# V2.net
KiCad netlist of a schematic drawn in EAGLE
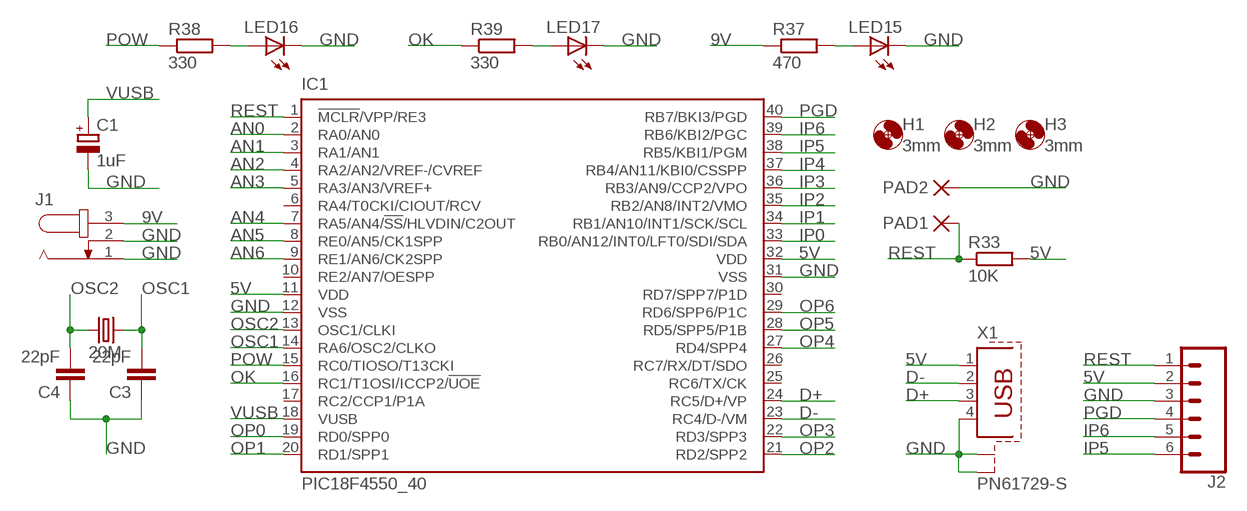
[diagram p0: schematic, sheet 1]
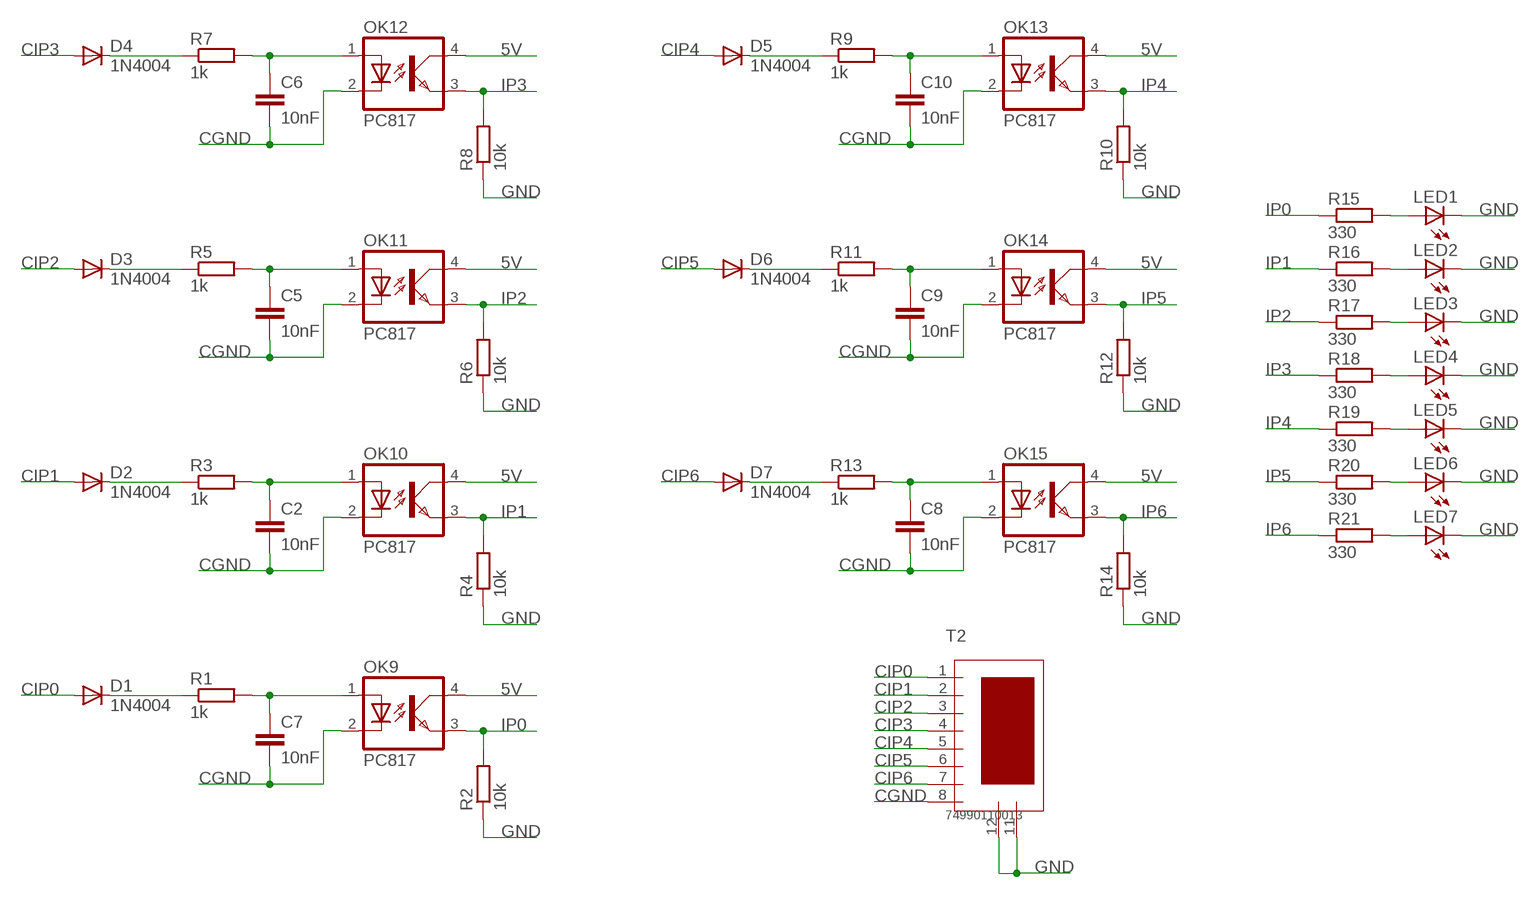
[diagram p1: schematic, sheet 2]
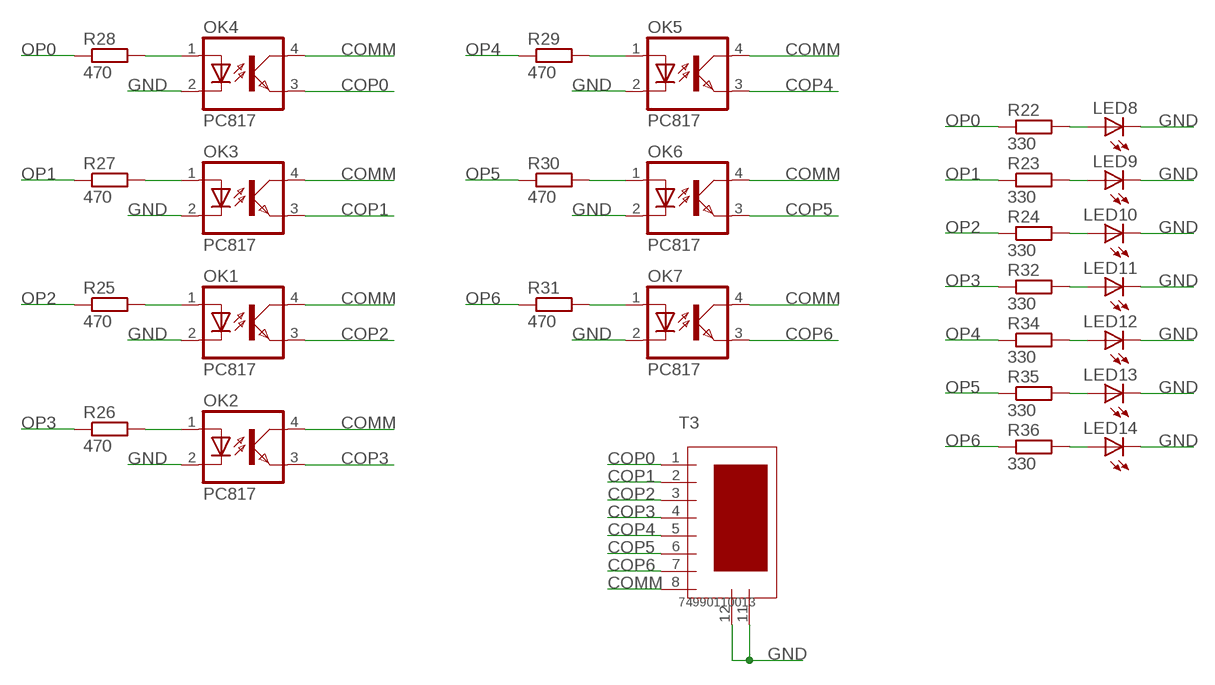
[diagram p2: schematic, sheet 3]
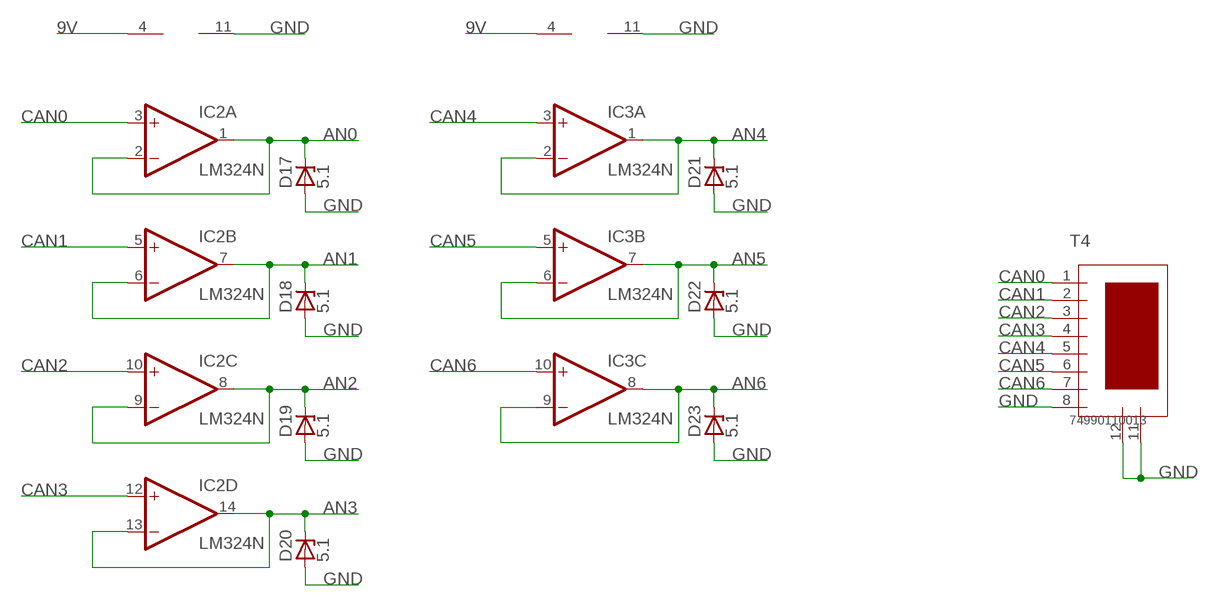
[diagram p3: schematic, sheet 4]

(export (version "E")
  (design (tool "Eeschema 10.0.6"))
  (components
    (comp (ref "LED8")
      (value "LED5MM")
      (footprint "eagle-import:LED5MM")
      (libsource (lib "eagle-import") (part "LED5MM"))
    )
    (comp (ref "LED9")
      (value "LED5MM")
      (footprint "eagle-import:LED5MM")
      (libsource (lib "eagle-import") (part "LED5MM"))
    )
    (comp (ref "LED10")
      (value "LED5MM")
      (footprint "eagle-import:LED5MM")
      (libsource (lib "eagle-import") (part "LED5MM"))
    )
    (comp (ref "LED11")
      (value "LED5MM")
      (footprint "eagle-import:LED5MM")
      (libsource (lib "eagle-import") (part "LED5MM"))
    )
    (comp (ref "LED12")
      (value "LED5MM")
      (footprint "eagle-import:LED5MM")
      (libsource (lib "eagle-import") (part "LED5MM"))
    )
    (comp (ref "LED13")
      (value "LED5MM")
      (footprint "eagle-import:LED5MM")
      (libsource (lib "eagle-import") (part "LED5MM"))
    )
    (comp (ref "LED14")
      (value "LED5MM")
      (footprint "eagle-import:LED5MM")
      (libsource (lib "eagle-import") (part "LED5MM"))
    )
    (comp (ref "OK1")
      (value "PC817")
      (footprint "eagle-import:DIL04")
      (fields (field (name "MPN") "PC817X4J000F"))
      (libsource (lib "eagle-import") (part "PC817"))
    )
    (comp (ref "OK2")
      (value "PC817")
      (footprint "eagle-import:DIL04")
      (fields (field (name "MPN") "PC817X4J000F"))
      (libsource (lib "eagle-import") (part "PC817"))
    )
    (comp (ref "OK3")
      (value "PC817")
      (footprint "eagle-import:DIL04")
      (fields (field (name "MPN") "PC817X4J000F"))
      (libsource (lib "eagle-import") (part "PC817"))
    )
    (comp (ref "OK4")
      (value "PC817")
      (footprint "eagle-import:DIL04")
      (fields (field (name "MPN") "PC817X4J000F"))
      (libsource (lib "eagle-import") (part "PC817"))
    )
    (comp (ref "OK5")
      (value "PC817")
      (footprint "eagle-import:DIL04")
      (fields (field (name "MPN") "PC817X4J000F"))
      (libsource (lib "eagle-import") (part "PC817"))
    )
    (comp (ref "OK6")
      (value "PC817")
      (footprint "eagle-import:DIL04")
      (fields (field (name "MPN") "PC817X4J000F"))
      (libsource (lib "eagle-import") (part "PC817"))
    )
    (comp (ref "OK7")
      (value "PC817")
      (footprint "eagle-import:DIL04")
      (fields (field (name "MPN") "PC817X4J000F"))
      (libsource (lib "eagle-import") (part "PC817"))
    )
    (comp (ref "R22")
      (value "330")
      (footprint "eagle-import:0207_10")
      (libsource (lib "eagle-import") (part "rcl_334_R-EU_0207/10"))
    )
    (comp (ref "R23")
      (value "330")
      (footprint "eagle-import:0207_10")
      (libsource (lib "eagle-import") (part "rcl_334_R-EU_0207/10"))
    )
    (comp (ref "R24")
      (value "330")
      (footprint "eagle-import:0207_10")
      (libsource (lib "eagle-import") (part "rcl_334_R-EU_0207/10"))
    )
    (comp (ref "R25")
      (value "470")
      (footprint "eagle-import:0207_10")
      (libsource (lib "eagle-import") (part "R-EU_0207/10"))
    )
    (comp (ref "R26")
      (value "470")
      (footprint "eagle-import:0207_10")
      (libsource (lib "eagle-import") (part "R-EU_0207/10"))
    )
    (comp (ref "R27")
      (value "470")
      (footprint "eagle-import:0207_10")
      (libsource (lib "eagle-import") (part "R-EU_0207/10"))
    )
    (comp (ref "R28")
      (value "470")
      (footprint "eagle-import:0207_10")
      (libsource (lib "eagle-import") (part "R-EU_0207/10"))
    )
    (comp (ref "R29")
      (value "470")
      (footprint "eagle-import:0207_10")
      (libsource (lib "eagle-import") (part "R-EU_0207/10"))
    )
    (comp (ref "R30")
      (value "470")
      (footprint "eagle-import:0207_10")
      (libsource (lib "eagle-import") (part "R-EU_0207/10"))
    )
    (comp (ref "R31")
      (value "470")
      (footprint "eagle-import:0207_10")
      (libsource (lib "eagle-import") (part "R-EU_0207/10"))
    )
    (comp (ref "R32")
      (value "330")
      (footprint "eagle-import:0207_10")
      (libsource (lib "eagle-import") (part "rcl_334_R-EU_0207/10"))
    )
    (comp (ref "R34")
      (value "330")
      (footprint "eagle-import:0207_10")
      (libsource (lib "eagle-import") (part "rcl_334_R-EU_0207/10"))
    )
    (comp (ref "R35")
      (value "330")
      (footprint "eagle-import:0207_10")
      (libsource (lib "eagle-import") (part "rcl_334_R-EU_0207/10"))
    )
    (comp (ref "R36")
      (value "330")
      (footprint "eagle-import:0207_10")
      (libsource (lib "eagle-import") (part "rcl_334_R-EU_0207/10"))
    )
    (comp (ref "T3")
      (value "74990110013")
      (footprint "eagle-import:01LAN_RJ45_10_00_STD")
      (libsource (lib "eagle-import") (part "74990110013"))
    )
    (comp (ref "C2")
      (value "10nF")
      (footprint "eagle-import:C5B2.5")
      (libsource (lib "eagle-import") (part "capacitor-wima_116_C5/2.5"))
    )
    (comp (ref "C5")
      (value "10nF")
      (footprint "eagle-import:C5B2.5")
      (libsource (lib "eagle-import") (part "capacitor-wima_116_C5/2.5"))
    )
    (comp (ref "C6")
      (value "10nF")
      (footprint "eagle-import:C5B2.5")
      (libsource (lib "eagle-import") (part "capacitor-wima_116_C5/2.5"))
    )
    (comp (ref "C7")
      (value "10nF")
      (footprint "eagle-import:C5B2.5")
      (libsource (lib "eagle-import") (part "capacitor-wima_116_C5/2.5"))
    )
    (comp (ref "C8")
      (value "10nF")
      (footprint "eagle-import:C5B2.5")
      (libsource (lib "eagle-import") (part "capacitor-wima_116_C5/2.5"))
    )
    (comp (ref "C9")
      (value "10nF")
      (footprint "eagle-import:C5B2.5")
      (libsource (lib "eagle-import") (part "capacitor-wima_116_C5/2.5"))
    )
    (comp (ref "C10")
      (value "10nF")
      (footprint "eagle-import:C5B2.5")
      (libsource (lib "eagle-import") (part "capacitor-wima_116_C5/2.5"))
    )
    (comp (ref "D1")
      (value "1N4004")
      (footprint "eagle-import:DO41-10")
      (libsource (lib "eagle-import") (part "1N4004"))
    )
    (comp (ref "D2")
      (value "1N4004")
      (footprint "eagle-import:DO41-10")
      (libsource (lib "eagle-import") (part "1N4004"))
    )
    (comp (ref "D3")
      (value "1N4004")
      (footprint "eagle-import:DO41-10")
      (libsource (lib "eagle-import") (part "1N4004"))
    )
    (comp (ref "D4")
      (value "1N4004")
      (footprint "eagle-import:DO41-10")
      (libsource (lib "eagle-import") (part "1N4004"))
    )
    (comp (ref "D5")
      (value "1N4004")
      (footprint "eagle-import:DO41-10")
      (libsource (lib "eagle-import") (part "1N4004"))
    )
    (comp (ref "D6")
      (value "1N4004")
      (footprint "eagle-import:DO41-10")
      (libsource (lib "eagle-import") (part "1N4004"))
    )
    (comp (ref "D7")
      (value "1N4004")
      (footprint "eagle-import:DO41-10")
      (libsource (lib "eagle-import") (part "1N4004"))
    )
    (comp (ref "LED1")
      (value "LED5MM")
      (footprint "eagle-import:LED5MM")
      (libsource (lib "eagle-import") (part "LED5MM"))
    )
    (comp (ref "LED2")
      (value "LED5MM")
      (footprint "eagle-import:LED5MM")
      (libsource (lib "eagle-import") (part "LED5MM"))
    )
    (comp (ref "LED3")
      (value "LED5MM")
      (footprint "eagle-import:LED5MM")
      (libsource (lib "eagle-import") (part "LED5MM"))
    )
    (comp (ref "LED4")
      (value "LED5MM")
      (footprint "eagle-import:LED5MM")
      (libsource (lib "eagle-import") (part "LED5MM"))
    )
    (comp (ref "LED5")
      (value "LED5MM")
      (footprint "eagle-import:LED5MM")
      (libsource (lib "eagle-import") (part "LED5MM"))
    )
    (comp (ref "LED6")
      (value "LED5MM")
      (footprint "eagle-import:LED5MM")
      (libsource (lib "eagle-import") (part "LED5MM"))
    )
    (comp (ref "LED7")
      (value "LED5MM")
      (footprint "eagle-import:LED5MM")
      (libsource (lib "eagle-import") (part "LED5MM"))
    )
    (comp (ref "OK9")
      (value "PC817")
      (footprint "eagle-import:DIL04")
      (fields (field (name "MPN") "PC817X4J000F"))
      (libsource (lib "eagle-import") (part "PC817"))
    )
    (comp (ref "OK10")
      (value "PC817")
      (footprint "eagle-import:DIL04")
      (fields (field (name "MPN") "PC817X4J000F"))
      (libsource (lib "eagle-import") (part "PC817"))
    )
    (comp (ref "OK11")
      (value "PC817")
      (footprint "eagle-import:DIL04")
      (fields (field (name "MPN") "PC817X4J000F"))
      (libsource (lib "eagle-import") (part "PC817"))
    )
    (comp (ref "OK12")
      (value "PC817")
      (footprint "eagle-import:DIL04")
      (fields (field (name "MPN") "PC817X4J000F"))
      (libsource (lib "eagle-import") (part "PC817"))
    )
    (comp (ref "OK13")
      (value "PC817")
      (footprint "eagle-import:DIL04")
      (fields (field (name "MPN") "PC817X4J000F"))
      (libsource (lib "eagle-import") (part "PC817"))
    )
    (comp (ref "OK14")
      (value "PC817")
      (footprint "eagle-import:DIL04")
      (fields (field (name "MPN") "PC817X4J000F"))
      (libsource (lib "eagle-import") (part "PC817"))
    )
    (comp (ref "OK15")
      (value "PC817")
      (footprint "eagle-import:DIL04")
      (fields (field (name "MPN") "PC817X4J000F"))
      (libsource (lib "eagle-import") (part "PC817"))
    )
    (comp (ref "R1")
      (value "1k")
      (footprint "eagle-import:0207_10")
      (libsource (lib "eagle-import") (part "rcl_334_R-EU_0207/10"))
    )
    (comp (ref "R2")
      (value "10k")
      (footprint "eagle-import:0207_10")
      (libsource (lib "eagle-import") (part "rcl_334_R-EU_0207/10"))
    )
    (comp (ref "R3")
      (value "1k")
      (footprint "eagle-import:0207_10")
      (libsource (lib "eagle-import") (part "rcl_334_R-EU_0207/10"))
    )
    (comp (ref "R4")
      (value "10k")
      (footprint "eagle-import:0207_10")
      (libsource (lib "eagle-import") (part "rcl_334_R-EU_0207/10"))
    )
    (comp (ref "R5")
      (value "1k")
      (footprint "eagle-import:0207_10")
      (libsource (lib "eagle-import") (part "rcl_334_R-EU_0207/10"))
    )
    (comp (ref "R6")
      (value "10k")
      (footprint "eagle-import:0207_10")
      (libsource (lib "eagle-import") (part "rcl_334_R-EU_0207/10"))
    )
    (comp (ref "R7")
      (value "1k")
      (footprint "eagle-import:0207_10")
      (libsource (lib "eagle-import") (part "rcl_334_R-EU_0207/10"))
    )
    (comp (ref "R8")
      (value "10k")
      (footprint "eagle-import:0207_10")
      (libsource (lib "eagle-import") (part "rcl_334_R-EU_0207/10"))
    )
    (comp (ref "R9")
      (value "1k")
      (footprint "eagle-import:0207_10")
      (libsource (lib "eagle-import") (part "rcl_334_R-EU_0207/10"))
    )
    (comp (ref "R10")
      (value "10k")
      (footprint "eagle-import:0207_10")
      (libsource (lib "eagle-import") (part "rcl_334_R-EU_0207/10"))
    )
    (comp (ref "R11")
      (value "1k")
      (footprint "eagle-import:0207_10")
      (libsource (lib "eagle-import") (part "rcl_334_R-EU_0207/10"))
    )
    (comp (ref "R12")
      (value "10k")
      (footprint "eagle-import:0207_10")
      (libsource (lib "eagle-import") (part "rcl_334_R-EU_0207/10"))
    )
    (comp (ref "R13")
      (value "1k")
      (footprint "eagle-import:0207_10")
      (libsource (lib "eagle-import") (part "rcl_334_R-EU_0207/10"))
    )
    (comp (ref "R14")
      (value "10k")
      (footprint "eagle-import:0207_10")
      (libsource (lib "eagle-import") (part "rcl_334_R-EU_0207/10"))
    )
    (comp (ref "R15")
      (value "330")
      (footprint "eagle-import:0207_10")
      (libsource (lib "eagle-import") (part "rcl_334_R-EU_0207/10"))
    )
    (comp (ref "R16")
      (value "330")
      (footprint "eagle-import:0207_10")
      (libsource (lib "eagle-import") (part "rcl_334_R-EU_0207/10"))
    )
    (comp (ref "R17")
      (value "330")
      (footprint "eagle-import:0207_10")
      (libsource (lib "eagle-import") (part "rcl_334_R-EU_0207/10"))
    )
    (comp (ref "R18")
      (value "330")
      (footprint "eagle-import:0207_10")
      (libsource (lib "eagle-import") (part "rcl_334_R-EU_0207/10"))
    )
    (comp (ref "R19")
      (value "330")
      (footprint "eagle-import:0207_10")
      (libsource (lib "eagle-import") (part "rcl_334_R-EU_0207/10"))
    )
    (comp (ref "R20")
      (value "330")
      (footprint "eagle-import:0207_10")
      (libsource (lib "eagle-import") (part "rcl_334_R-EU_0207/10"))
    )
    (comp (ref "R21")
      (value "330")
      (footprint "eagle-import:0207_10")
      (libsource (lib "eagle-import") (part "rcl_334_R-EU_0207/10"))
    )
    (comp (ref "T2")
      (value "74990110013")
      (footprint "eagle-import:01LAN_RJ45_10_00_STD")
      (libsource (lib "eagle-import") (part "74990110013"))
    )
    (comp (ref "D17")
      (value "5.1")
      (footprint "eagle-import:ZDIO-10")
      (libsource (lib "eagle-import") (part "ZENER-DIODEZD-10"))
    )
    (comp (ref "D18")
      (value "5.1")
      (footprint "eagle-import:ZDIO-10")
      (libsource (lib "eagle-import") (part "ZENER-DIODEZD-10"))
    )
    (comp (ref "D19")
      (value "5.1")
      (footprint "eagle-import:ZDIO-10")
      (libsource (lib "eagle-import") (part "ZENER-DIODEZD-10"))
    )
    (comp (ref "D20")
      (value "5.1")
      (footprint "eagle-import:ZDIO-10")
      (libsource (lib "eagle-import") (part "ZENER-DIODEZD-10"))
    )
    (comp (ref "D21")
      (value "5.1")
      (footprint "eagle-import:ZDIO-10")
      (libsource (lib "eagle-import") (part "ZENER-DIODEZD-10"))
    )
    (comp (ref "D22")
      (value "5.1")
      (footprint "eagle-import:ZDIO-10")
      (libsource (lib "eagle-import") (part "ZENER-DIODEZD-10"))
    )
    (comp (ref "D23")
      (value "5.1")
      (footprint "eagle-import:ZDIO-10")
      (libsource (lib "eagle-import") (part "ZENER-DIODEZD-10"))
    )
    (comp (ref "IC2")
      (value "LM324N")
      (footprint "eagle-import:DIL14")
      (libsource (lib "eagle-import") (part "LM324N"))
    )
    (comp (ref "IC3")
      (value "LM324N")
      (footprint "eagle-import:DIL14")
      (libsource (lib "eagle-import") (part "LM324N"))
    )
    (comp (ref "T4")
      (value "74990110013")
      (footprint "eagle-import:01LAN_RJ45_10_00_STD")
      (libsource (lib "eagle-import") (part "74990110013"))
    )
    (comp (ref "20M")
      (value "CRYSTALHC18U-V")
      (footprint "eagle-import:HC18U-V")
      (libsource (lib "eagle-import") (part "CRYSTALHC18U-V"))
    )
    (comp (ref "C1")
      (value "1uF")
      (footprint "eagle-import:E2-5")
      (libsource (lib "eagle-import") (part "CPOL-EUE2-5"))
    )
    (comp (ref "C3")
      (value "22pF")
      (footprint "eagle-import:C5B2.5")
      (libsource (lib "eagle-import") (part "C5/2.5"))
    )
    (comp (ref "C4")
      (value "22pF")
      (footprint "eagle-import:C5B2.5")
      (libsource (lib "eagle-import") (part "C5/2.5"))
    )
    (comp (ref "H1")
      (value "3mm")
      (footprint "eagle-import:3,0")
      (libsource (lib "eagle-import") (part "MOUNT-HOLE3.0"))
    )
    (comp (ref "H2")
      (value "3mm")
      (footprint "eagle-import:3,0")
      (libsource (lib "eagle-import") (part "MOUNT-HOLE3.0"))
    )
    (comp (ref "H3")
      (value "3mm")
      (footprint "eagle-import:3,0")
      (libsource (lib "eagle-import") (part "MOUNT-HOLE3.0"))
    )
    (comp (ref "IC1")
      (value "PIC18F4550_40")
      (footprint "eagle-import:DIL40")
      (fields (field (name "MF") "MICROCHIP") (field (name "MPN") "PIC18F4550-I/P"))
      (libsource (lib "eagle-import") (part "PIC18F4_40550"))
    )
    (comp (ref "J1")
      (value "JACK-PLUG0")
      (footprint "eagle-import:SPC4077")
      (libsource (lib "eagle-import") (part "JACK-PLUG0"))
    )
    (comp (ref "J2")
      (value "CONN_06LONGPADS")
      (footprint "eagle-import:1X06_LONGPADS")
      (libsource (lib "eagle-import") (part "CONN_06LONGPADS"))
    )
    (comp (ref "LED15")
      (value "LED5MM")
      (footprint "eagle-import:LED5MM")
      (libsource (lib "eagle-import") (part "LED5MM"))
    )
    (comp (ref "LED16")
      (value "LED5MM")
      (footprint "eagle-import:LED5MM")
      (libsource (lib "eagle-import") (part "LED5MM"))
    )
    (comp (ref "LED17")
      (value "LED5MM")
      (footprint "eagle-import:LED5MM")
      (libsource (lib "eagle-import") (part "LED5MM"))
    )
    (comp (ref "PAD1")
      (value "PAD-0320")
      (footprint "eagle-import:0320")
      (libsource (lib "eagle-import") (part "PAD-0320"))
    )
    (comp (ref "PAD2")
      (value "PAD-0320")
      (footprint "eagle-import:0320")
      (libsource (lib "eagle-import") (part "PAD-0320"))
    )
    (comp (ref "R33")
      (value "10K")
      (footprint "eagle-import:0207_10")
      (libsource (lib "eagle-import") (part "R-EU_0207/10"))
    )
    (comp (ref "R37")
      (value "470")
      (footprint "eagle-import:0207_10")
      (libsource (lib "eagle-import") (part "rcl_334_R-EU_0207/10"))
    )
    (comp (ref "R38")
      (value "330")
      (footprint "eagle-import:0207_10")
      (libsource (lib "eagle-import") (part "rcl_334_R-EU_0207/10"))
    )
    (comp (ref "R39")
      (value "330")
      (footprint "eagle-import:0207_10")
      (libsource (lib "eagle-import") (part "rcl_334_R-EU_0207/10"))
    )
    (comp (ref "X1")
      (value "PN61729-S")
      (footprint "eagle-import:PN61729-S")
      (libsource (lib "eagle-import") (part "PN61729-S"))
    )
  )
  (nets
    (net (code "1") (name "5V") (class "Default")
      (node (ref "IC1") (pin "11") (pinfunction "VDD_11") (pintype "power_in"))
      (node (ref "IC1") (pin "32") (pinfunction "VDD_32") (pintype "power_in"))
      (node (ref "J2") (pin "2") (pinfunction "2_2") (pintype "passive"))
      (node (ref "OK10") (pin "4") (pinfunction "COL_4") (pintype "passive"))
      (node (ref "OK11") (pin "4") (pinfunction "COL_4") (pintype "passive"))
      (node (ref "OK12") (pin "4") (pinfunction "COL_4") (pintype "passive"))
      (node (ref "OK13") (pin "4") (pinfunction "COL_4") (pintype "passive"))
      (node (ref "OK14") (pin "4") (pinfunction "COL_4") (pintype "passive"))
      (node (ref "OK15") (pin "4") (pinfunction "COL_4") (pintype "passive"))
      (node (ref "OK9") (pin "4") (pinfunction "COL_4") (pintype "passive"))
      (node (ref "R33") (pin "2") (pinfunction "2_2") (pintype "passive"))
      (node (ref "X1") (pin "1") (pinfunction "1_1") (pintype "passive"))
    )
    (net (code "2") (name "9V") (class "Default")
      (node (ref "IC2") (pin "4") (pinfunction "V+_4") (pintype "power_in"))
      (node (ref "IC3") (pin "4") (pinfunction "V+_4") (pintype "power_in"))
      (node (ref "J1") (pin "3") (pinfunction "3_3") (pintype "passive"))
      (node (ref "R37") (pin "1") (pinfunction "1_1") (pintype "passive"))
    )
    (net (code "3") (name "AN0") (class "Default")
      (node (ref "D17") (pin "C") (pinfunction "C_C") (pintype "passive"))
      (node (ref "IC1") (pin "2") (pinfunction "RA0/AN0_2") (pintype "bidirectional"))
      (node (ref "IC2") (pin "1") (pinfunction "OUT_1") (pintype "output"))
      (node (ref "IC2") (pin "2") (pinfunction "-IN_2") (pintype "input"))
    )
    (net (code "4") (name "AN1") (class "Default")
      (node (ref "D18") (pin "C") (pinfunction "C_C") (pintype "passive"))
      (node (ref "IC1") (pin "3") (pinfunction "RA1/AN1_3") (pintype "bidirectional"))
      (node (ref "IC2") (pin "6") (pinfunction "-IN_6") (pintype "input"))
      (node (ref "IC2") (pin "7") (pinfunction "OUT_7") (pintype "output"))
    )
    (net (code "5") (name "AN2") (class "Default")
      (node (ref "D19") (pin "C") (pinfunction "C_C") (pintype "passive"))
      (node (ref "IC1") (pin "4") (pinfunction "RA2/AN2/VREF-/CVREF_4") (pintype "bidirectional"))
      (node (ref "IC2") (pin "8") (pinfunction "OUT_8") (pintype "output"))
      (node (ref "IC2") (pin "9") (pinfunction "-IN_9") (pintype "input"))
    )
    (net (code "6") (name "AN3") (class "Default")
      (node (ref "D20") (pin "C") (pinfunction "C_C") (pintype "passive"))
      (node (ref "IC1") (pin "5") (pinfunction "RA3/AN3/VREF+_5") (pintype "bidirectional"))
      (node (ref "IC2") (pin "13") (pinfunction "-IN_13") (pintype "input"))
      (node (ref "IC2") (pin "14") (pinfunction "OUT_14") (pintype "output"))
    )
    (net (code "7") (name "AN4") (class "Default")
      (node (ref "D21") (pin "C") (pinfunction "C_C") (pintype "passive"))
      (node (ref "IC1") (pin "7") (pinfunction "RA5/AN4/~{SS}/HLVDIN/C2OUT_7") (pintype "bidirectional"))
      (node (ref "IC3") (pin "1") (pinfunction "OUT_1") (pintype "output"))
      (node (ref "IC3") (pin "2") (pinfunction "-IN_2") (pintype "input"))
    )
    (net (code "8") (name "AN5") (class "Default")
      (node (ref "D22") (pin "C") (pinfunction "C_C") (pintype "passive"))
      (node (ref "IC1") (pin "8") (pinfunction "RE0/AN5/CK1SPP_8") (pintype "bidirectional"))
      (node (ref "IC3") (pin "6") (pinfunction "-IN_6") (pintype "input"))
      (node (ref "IC3") (pin "7") (pinfunction "OUT_7") (pintype "output"))
    )
    (net (code "9") (name "AN6") (class "Default")
      (node (ref "D23") (pin "C") (pinfunction "C_C") (pintype "passive"))
      (node (ref "IC1") (pin "9") (pinfunction "RE1/AN6/CK2SPP_9") (pintype "bidirectional"))
      (node (ref "IC3") (pin "8") (pinfunction "OUT_8") (pintype "output"))
      (node (ref "IC3") (pin "9") (pinfunction "-IN_9") (pintype "input"))
    )
    (net (code "10") (name "CAN0") (class "Default")
      (node (ref "IC2") (pin "3") (pinfunction "+IN_3") (pintype "input"))
      (node (ref "T4") (pin "1") (pinfunction "1_1") (pintype "passive"))
    )
    (net (code "11") (name "CAN1") (class "Default")
      (node (ref "IC2") (pin "5") (pinfunction "+IN_5") (pintype "input"))
      (node (ref "T4") (pin "2") (pinfunction "2_2") (pintype "passive"))
    )
    (net (code "12") (name "CAN2") (class "Default")
      (node (ref "IC2") (pin "10") (pinfunction "+IN_10") (pintype "input"))
      (node (ref "T4") (pin "3") (pinfunction "3_3") (pintype "passive"))
    )
    (net (code "13") (name "CAN3") (class "Default")
      (node (ref "IC2") (pin "12") (pinfunction "+IN_12") (pintype "input"))
      (node (ref "T4") (pin "4") (pinfunction "4_4") (pintype "passive"))
    )
    (net (code "14") (name "CAN4") (class "Default")
      (node (ref "IC3") (pin "3") (pinfunction "+IN_3") (pintype "input"))
      (node (ref "T4") (pin "5") (pinfunction "5_5") (pintype "passive"))
    )
    (net (code "15") (name "CAN5") (class "Default")
      (node (ref "IC3") (pin "5") (pinfunction "+IN_5") (pintype "input"))
      (node (ref "T4") (pin "6") (pinfunction "6_6") (pintype "passive"))
    )
    (net (code "16") (name "CAN6") (class "Default")
      (node (ref "IC3") (pin "10") (pinfunction "+IN_10") (pintype "input"))
      (node (ref "T4") (pin "7") (pinfunction "8_7") (pintype "passive"))
    )
    (net (code "17") (name "CGND") (class "Default")
      (node (ref "C10") (pin "2") (pinfunction "2_2") (pintype "passive"))
      (node (ref "C2") (pin "2") (pinfunction "2_2") (pintype "passive"))
      (node (ref "C5") (pin "2") (pinfunction "2_2") (pintype "passive"))
      (node (ref "C6") (pin "2") (pinfunction "2_2") (pintype "passive"))
      (node (ref "C7") (pin "2") (pinfunction "2_2") (pintype "passive"))
      (node (ref "C8") (pin "2") (pinfunction "2_2") (pintype "passive"))
      (node (ref "C9") (pin "2") (pinfunction "2_2") (pintype "passive"))
      (node (ref "OK10") (pin "2") (pinfunction "C_2") (pintype "passive"))
      (node (ref "OK11") (pin "2") (pinfunction "C_2") (pintype "passive"))
      (node (ref "OK12") (pin "2") (pinfunction "C_2") (pintype "passive"))
      (node (ref "OK13") (pin "2") (pinfunction "C_2") (pintype "passive"))
      (node (ref "OK14") (pin "2") (pinfunction "C_2") (pintype "passive"))
      (node (ref "OK15") (pin "2") (pinfunction "C_2") (pintype "passive"))
      (node (ref "OK9") (pin "2") (pinfunction "C_2") (pintype "passive"))
      (node (ref "T2") (pin "8") (pinfunction "7_8") (pintype "passive"))
    )
    (net (code "18") (name "CIP0") (class "Default")
      (node (ref "D1") (pin "A") (pinfunction "A_A") (pintype "passive"))
      (node (ref "T2") (pin "1") (pinfunction "1_1") (pintype "passive"))
    )
    (net (code "19") (name "CIP1") (class "Default")
      (node (ref "D2") (pin "A") (pinfunction "A_A") (pintype "passive"))
      (node (ref "T2") (pin "2") (pinfunction "2_2") (pintype "passive"))
    )
    (net (code "20") (name "CIP2") (class "Default")
      (node (ref "D3") (pin "A") (pinfunction "A_A") (pintype "passive"))
      (node (ref "T2") (pin "3") (pinfunction "3_3") (pintype "passive"))
    )
    (net (code "21") (name "CIP3") (class "Default")
      (node (ref "D4") (pin "A") (pinfunction "A_A") (pintype "passive"))
      (node (ref "T2") (pin "4") (pinfunction "4_4") (pintype "passive"))
    )
    (net (code "22") (name "CIP4") (class "Default")
      (node (ref "D5") (pin "A") (pinfunction "A_A") (pintype "passive"))
      (node (ref "T2") (pin "5") (pinfunction "5_5") (pintype "passive"))
    )
    (net (code "23") (name "CIP5") (class "Default")
      (node (ref "D6") (pin "A") (pinfunction "A_A") (pintype "passive"))
      (node (ref "T2") (pin "6") (pinfunction "6_6") (pintype "passive"))
    )
    (net (code "24") (name "CIP6") (class "Default")
      (node (ref "D7") (pin "A") (pinfunction "A_A") (pintype "passive"))
      (node (ref "T2") (pin "7") (pinfunction "8_7") (pintype "passive"))
    )
    (net (code "25") (name "COMM") (class "Default")
      (node (ref "OK1") (pin "4") (pinfunction "COL_4") (pintype "passive"))
      (node (ref "OK2") (pin "4") (pinfunction "COL_4") (pintype "passive"))
      (node (ref "OK3") (pin "4") (pinfunction "COL_4") (pintype "passive"))
      (node (ref "OK4") (pin "4") (pinfunction "COL_4") (pintype "passive"))
      (node (ref "OK5") (pin "4") (pinfunction "COL_4") (pintype "passive"))
      (node (ref "OK6") (pin "4") (pinfunction "COL_4") (pintype "passive"))
      (node (ref "OK7") (pin "4") (pinfunction "COL_4") (pintype "passive"))
      (node (ref "T3") (pin "8") (pinfunction "7_8") (pintype "passive"))
    )
    (net (code "26") (name "COP0") (class "Default")
      (node (ref "OK4") (pin "3") (pinfunction "EMIT_3") (pintype "passive"))
      (node (ref "T3") (pin "1") (pinfunction "1_1") (pintype "passive"))
    )
    (net (code "27") (name "COP1") (class "Default")
      (node (ref "OK3") (pin "3") (pinfunction "EMIT_3") (pintype "passive"))
      (node (ref "T3") (pin "2") (pinfunction "2_2") (pintype "passive"))
    )
    (net (code "28") (name "COP2") (class "Default")
      (node (ref "OK1") (pin "3") (pinfunction "EMIT_3") (pintype "passive"))
      (node (ref "T3") (pin "3") (pinfunction "3_3") (pintype "passive"))
    )
    (net (code "29") (name "COP3") (class "Default")
      (node (ref "OK2") (pin "3") (pinfunction "EMIT_3") (pintype "passive"))
      (node (ref "T3") (pin "4") (pinfunction "4_4") (pintype "passive"))
    )
    (net (code "30") (name "COP4") (class "Default")
      (node (ref "OK5") (pin "3") (pinfunction "EMIT_3") (pintype "passive"))
      (node (ref "T3") (pin "5") (pinfunction "5_5") (pintype "passive"))
    )
    (net (code "31") (name "COP5") (class "Default")
      (node (ref "OK6") (pin "3") (pinfunction "EMIT_3") (pintype "passive"))
      (node (ref "T3") (pin "6") (pinfunction "6_6") (pintype "passive"))
    )
    (net (code "32") (name "COP6") (class "Default")
      (node (ref "OK7") (pin "3") (pinfunction "EMIT_3") (pintype "passive"))
      (node (ref "T3") (pin "7") (pinfunction "8_7") (pintype "passive"))
    )
    (net (code "33") (name "D+") (class "Default")
      (node (ref "IC1") (pin "24") (pinfunction "RC5/D+/VP_24") (pintype "bidirectional"))
      (node (ref "X1") (pin "3") (pinfunction "3_3") (pintype "passive"))
    )
    (net (code "34") (name "D-") (class "Default")
      (node (ref "IC1") (pin "23") (pinfunction "RC4/D-/VM_23") (pintype "bidirectional"))
      (node (ref "X1") (pin "2") (pinfunction "2_2") (pintype "passive"))
    )
    (net (code "35") (name "GND") (class "Default")
      (node (ref "C1") (pin "-") (pinfunction "-_-") (pintype "passive"))
      (node (ref "C3") (pin "1") (pinfunction "1_1") (pintype "passive"))
      (node (ref "C4") (pin "1") (pinfunction "1_1") (pintype "passive"))
      (node (ref "D17") (pin "A") (pinfunction "A_A") (pintype "passive"))
      (node (ref "D18") (pin "A") (pinfunction "A_A") (pintype "passive"))
      (node (ref "D19") (pin "A") (pinfunction "A_A") (pintype "passive"))
      (node (ref "D20") (pin "A") (pinfunction "A_A") (pintype "passive"))
      (node (ref "D21") (pin "A") (pinfunction "A_A") (pintype "passive"))
      (node (ref "D22") (pin "A") (pinfunction "A_A") (pintype "passive"))
      (node (ref "D23") (pin "A") (pinfunction "A_A") (pintype "passive"))
      (node (ref "IC1") (pin "12") (pinfunction "VSS_12") (pintype "power_in"))
      (node (ref "IC1") (pin "31") (pinfunction "VSS_31") (pintype "power_in"))
      (node (ref "IC2") (pin "11") (pinfunction "V-_11") (pintype "power_in"))
      (node (ref "IC3") (pin "11") (pinfunction "V-_11") (pintype "power_in"))
      (node (ref "J1") (pin "1") (pinfunction "1_1") (pintype "passive"))
      (node (ref "J1") (pin "2") (pinfunction "2_2") (pintype "passive"))
      (node (ref "J2") (pin "3") (pinfunction "3_3") (pintype "passive"))
      (node (ref "LED1") (pin "K") (pinfunction "C_K") (pintype "passive"))
      (node (ref "LED10") (pin "K") (pinfunction "C_K") (pintype "passive"))
      (node (ref "LED11") (pin "K") (pinfunction "C_K") (pintype "passive"))
      (node (ref "LED12") (pin "K") (pinfunction "C_K") (pintype "passive"))
      (node (ref "LED13") (pin "K") (pinfunction "C_K") (pintype "passive"))
      (node (ref "LED14") (pin "K") (pinfunction "C_K") (pintype "passive"))
      (node (ref "LED15") (pin "K") (pinfunction "C_K") (pintype "passive"))
      (node (ref "LED16") (pin "K") (pinfunction "C_K") (pintype "passive"))
      (node (ref "LED17") (pin "K") (pinfunction "C_K") (pintype "passive"))
      (node (ref "LED2") (pin "K") (pinfunction "C_K") (pintype "passive"))
      (node (ref "LED3") (pin "K") (pinfunction "C_K") (pintype "passive"))
      (node (ref "LED4") (pin "K") (pinfunction "C_K") (pintype "passive"))
      (node (ref "LED5") (pin "K") (pinfunction "C_K") (pintype "passive"))
      (node (ref "LED6") (pin "K") (pinfunction "C_K") (pintype "passive"))
      (node (ref "LED7") (pin "K") (pinfunction "C_K") (pintype "passive"))
      (node (ref "LED8") (pin "K") (pinfunction "C_K") (pintype "passive"))
      (node (ref "LED9") (pin "K") (pinfunction "C_K") (pintype "passive"))
      (node (ref "OK1") (pin "2") (pinfunction "C_2") (pintype "passive"))
      (node (ref "OK2") (pin "2") (pinfunction "C_2") (pintype "passive"))
      (node (ref "OK3") (pin "2") (pinfunction "C_2") (pintype "passive"))
      (node (ref "OK4") (pin "2") (pinfunction "C_2") (pintype "passive"))
      (node (ref "OK5") (pin "2") (pinfunction "C_2") (pintype "passive"))
      (node (ref "OK6") (pin "2") (pinfunction "C_2") (pintype "passive"))
      (node (ref "OK7") (pin "2") (pinfunction "C_2") (pintype "passive"))
      (node (ref "PAD2") (pin "P$1") (pinfunction "P_P$1") (pintype "passive"))
      (node (ref "R10") (pin "1") (pinfunction "1_1") (pintype "passive"))
      (node (ref "R12") (pin "1") (pinfunction "1_1") (pintype "passive"))
      (node (ref "R14") (pin "1") (pinfunction "1_1") (pintype "passive"))
      (node (ref "R2") (pin "1") (pinfunction "1_1") (pintype "passive"))
      (node (ref "R4") (pin "1") (pinfunction "1_1") (pintype "passive"))
      (node (ref "R6") (pin "1") (pinfunction "1_1") (pintype "passive"))
      (node (ref "R8") (pin "1") (pinfunction "1_1") (pintype "passive"))
      (node (ref "T2") (pin "11") (pinfunction "9_11") (pintype "passive"))
      (node (ref "T2") (pin "12") (pinfunction "10_12") (pintype "passive"))
      (node (ref "T3") (pin "11") (pinfunction "9_11") (pintype "passive"))
      (node (ref "T3") (pin "12") (pinfunction "10_12") (pintype "passive"))
      (node (ref "T4") (pin "11") (pinfunction "9_11") (pintype "passive"))
      (node (ref "T4") (pin "12") (pinfunction "10_12") (pintype "passive"))
      (node (ref "T4") (pin "8") (pinfunction "7_8") (pintype "passive"))
      (node (ref "X1") (pin "4") (pinfunction "4_4") (pintype "passive"))
      (node (ref "X1") (pin "S1") (pinfunction "S1_S1") (pintype "passive"))
      (node (ref "X1") (pin "S2") (pinfunction "S2_S2") (pintype "passive"))
    )
    (net (code "36") (name "IP0") (class "Default")
      (node (ref "IC1") (pin "33") (pinfunction "RB0/AN12/INT0/LFT0/SDI/SDA_33") (pintype "bidirectional"))
      (node (ref "OK9") (pin "3") (pinfunction "EMIT_3") (pintype "passive"))
      (node (ref "R15") (pin "1") (pinfunction "1_1") (pintype "passive"))
      (node (ref "R2") (pin "2") (pinfunction "2_2") (pintype "passive"))
    )
    (net (code "37") (name "IP1") (class "Default")
      (node (ref "IC1") (pin "34") (pinfunction "RB1/AN10/INT1/SCK/SCL_34") (pintype "bidirectional"))
      (node (ref "OK10") (pin "3") (pinfunction "EMIT_3") (pintype "passive"))
      (node (ref "R16") (pin "1") (pinfunction "1_1") (pintype "passive"))
      (node (ref "R4") (pin "2") (pinfunction "2_2") (pintype "passive"))
    )
    (net (code "38") (name "IP2") (class "Default")
      (node (ref "IC1") (pin "35") (pinfunction "RB2/AN8/INT2/VMO_35") (pintype "bidirectional"))
      (node (ref "OK11") (pin "3") (pinfunction "EMIT_3") (pintype "passive"))
      (node (ref "R17") (pin "1") (pinfunction "1_1") (pintype "passive"))
      (node (ref "R6") (pin "2") (pinfunction "2_2") (pintype "passive"))
    )
    (net (code "39") (name "IP3") (class "Default")
      (node (ref "IC1") (pin "36") (pinfunction "RB3/AN9/CCP2/VPO_36") (pintype "bidirectional"))
      (node (ref "OK12") (pin "3") (pinfunction "EMIT_3") (pintype "passive"))
      (node (ref "R18") (pin "1") (pinfunction "1_1") (pintype "passive"))
      (node (ref "R8") (pin "2") (pinfunction "2_2") (pintype "passive"))
    )
    (net (code "40") (name "IP4") (class "Default")
      (node (ref "IC1") (pin "37") (pinfunction "RB4/AN11/KBI0/CSSPP_37") (pintype "bidirectional"))
      (node (ref "OK13") (pin "3") (pinfunction "EMIT_3") (pintype "passive"))
      (node (ref "R10") (pin "2") (pinfunction "2_2") (pintype "passive"))
      (node (ref "R19") (pin "1") (pinfunction "1_1") (pintype "passive"))
    )
    (net (code "41") (name "IP5") (class "Default")
      (node (ref "IC1") (pin "38") (pinfunction "RB5/KBI1/PGM_38") (pintype "bidirectional"))
      (node (ref "J2") (pin "6") (pinfunction "6_6") (pintype "passive"))
      (node (ref "OK14") (pin "3") (pinfunction "EMIT_3") (pintype "passive"))
      (node (ref "R12") (pin "2") (pinfunction "2_2") (pintype "passive"))
      (node (ref "R20") (pin "1") (pinfunction "1_1") (pintype "passive"))
    )
    (net (code "42") (name "IP6") (class "Default")
      (node (ref "IC1") (pin "39") (pinfunction "RB6/KBI2/PGC_39") (pintype "bidirectional"))
      (node (ref "J2") (pin "5") (pinfunction "5_5") (pintype "passive"))
      (node (ref "OK15") (pin "3") (pinfunction "EMIT_3") (pintype "passive"))
      (node (ref "R14") (pin "2") (pinfunction "2_2") (pintype "passive"))
      (node (ref "R21") (pin "1") (pinfunction "1_1") (pintype "passive"))
    )
    (net (code "43") (name "Net-(D1-PadC)") (class "Default")
      (node (ref "D1") (pin "C") (pinfunction "C_C") (pintype "passive"))
      (node (ref "R1") (pin "1") (pinfunction "1_1") (pintype "passive"))
    )
    (net (code "44") (name "Net-(D2-PadC)") (class "Default")
      (node (ref "D2") (pin "C") (pinfunction "C_C") (pintype "passive"))
      (node (ref "R3") (pin "1") (pinfunction "1_1") (pintype "passive"))
    )
    (net (code "45") (name "Net-(D3-PadC)") (class "Default")
      (node (ref "D3") (pin "C") (pinfunction "C_C") (pintype "passive"))
      (node (ref "R5") (pin "1") (pinfunction "1_1") (pintype "passive"))
    )
    (net (code "46") (name "Net-(D4-PadC)") (class "Default")
      (node (ref "D4") (pin "C") (pinfunction "C_C") (pintype "passive"))
      (node (ref "R7") (pin "1") (pinfunction "1_1") (pintype "passive"))
    )
    (net (code "47") (name "Net-(D5-PadC)") (class "Default")
      (node (ref "D5") (pin "C") (pinfunction "C_C") (pintype "passive"))
      (node (ref "R9") (pin "1") (pinfunction "1_1") (pintype "passive"))
    )
    (net (code "48") (name "Net-(D6-PadC)") (class "Default")
      (node (ref "D6") (pin "C") (pinfunction "C_C") (pintype "passive"))
      (node (ref "R11") (pin "1") (pinfunction "1_1") (pintype "passive"))
    )
    (net (code "49") (name "Net-(D7-PadC)") (class "Default")
      (node (ref "D7") (pin "C") (pinfunction "C_C") (pintype "passive"))
      (node (ref "R13") (pin "1") (pinfunction "1_1") (pintype "passive"))
    )
    (net (code "50") (name "Net-(LED1-PadA)") (class "Default")
      (node (ref "LED1") (pin "A") (pinfunction "A_A") (pintype "passive"))
      (node (ref "R15") (pin "2") (pinfunction "2_2") (pintype "passive"))
    )
    (net (code "51") (name "Net-(LED2-PadA)") (class "Default")
      (node (ref "LED2") (pin "A") (pinfunction "A_A") (pintype "passive"))
      (node (ref "R16") (pin "2") (pinfunction "2_2") (pintype "passive"))
    )
    (net (code "52") (name "Net-(LED3-PadA)") (class "Default")
      (node (ref "LED3") (pin "A") (pinfunction "A_A") (pintype "passive"))
      (node (ref "R17") (pin "2") (pinfunction "2_2") (pintype "passive"))
    )
    (net (code "53") (name "Net-(LED4-PadA)") (class "Default")
      (node (ref "LED4") (pin "A") (pinfunction "A_A") (pintype "passive"))
      (node (ref "R18") (pin "2") (pinfunction "2_2") (pintype "passive"))
    )
    (net (code "54") (name "Net-(LED5-PadA)") (class "Default")
      (node (ref "LED5") (pin "A") (pinfunction "A_A") (pintype "passive"))
      (node (ref "R19") (pin "2") (pinfunction "2_2") (pintype "passive"))
    )
    (net (code "55") (name "Net-(LED6-PadA)") (class "Default")
      (node (ref "LED6") (pin "A") (pinfunction "A_A") (pintype "passive"))
      (node (ref "R20") (pin "2") (pinfunction "2_2") (pintype "passive"))
    )
    (net (code "56") (name "Net-(LED7-PadA)") (class "Default")
      (node (ref "LED7") (pin "A") (pinfunction "A_A") (pintype "passive"))
      (node (ref "R21") (pin "2") (pinfunction "2_2") (pintype "passive"))
    )
    (net (code "57") (name "Net-(LED8-PadA)") (class "Default")
      (node (ref "LED8") (pin "A") (pinfunction "A_A") (pintype "passive"))
      (node (ref "R22") (pin "2") (pinfunction "2_2") (pintype "passive"))
    )
    (net (code "58") (name "Net-(LED9-PadA)") (class "Default")
      (node (ref "LED9") (pin "A") (pinfunction "A_A") (pintype "passive"))
      (node (ref "R23") (pin "2") (pinfunction "2_2") (pintype "passive"))
    )
    (net (code "59") (name "Net-(LED10-PadA)") (class "Default")
      (node (ref "LED10") (pin "A") (pinfunction "A_A") (pintype "passive"))
      (node (ref "R24") (pin "2") (pinfunction "2_2") (pintype "passive"))
    )
    (net (code "60") (name "Net-(LED11-PadA)") (class "Default")
      (node (ref "LED11") (pin "A") (pinfunction "A_A") (pintype "passive"))
      (node (ref "R32") (pin "2") (pinfunction "2_2") (pintype "passive"))
    )
    (net (code "61") (name "Net-(LED12-PadA)") (class "Default")
      (node (ref "LED12") (pin "A") (pinfunction "A_A") (pintype "passive"))
      (node (ref "R34") (pin "2") (pinfunction "2_2") (pintype "passive"))
    )
    (net (code "62") (name "Net-(LED13-PadA)") (class "Default")
      (node (ref "LED13") (pin "A") (pinfunction "A_A") (pintype "passive"))
      (node (ref "R35") (pin "2") (pinfunction "2_2") (pintype "passive"))
    )
    (net (code "63") (name "Net-(LED14-PadA)") (class "Default")
      (node (ref "LED14") (pin "A") (pinfunction "A_A") (pintype "passive"))
      (node (ref "R36") (pin "2") (pinfunction "2_2") (pintype "passive"))
    )
    (net (code "64") (name "Net-(LED15-PadA)") (class "Default")
      (node (ref "LED15") (pin "A") (pinfunction "A_A") (pintype "passive"))
      (node (ref "R37") (pin "2") (pinfunction "2_2") (pintype "passive"))
    )
    (net (code "65") (name "Net-(LED16-PadA)") (class "Default")
      (node (ref "LED16") (pin "A") (pinfunction "A_A") (pintype "passive"))
      (node (ref "R38") (pin "2") (pinfunction "2_2") (pintype "passive"))
    )
    (net (code "66") (name "Net-(LED17-PadA)") (class "Default")
      (node (ref "LED17") (pin "A") (pinfunction "A_A") (pintype "passive"))
      (node (ref "R39") (pin "2") (pinfunction "2_2") (pintype "passive"))
    )
    (net (code "67") (name "Net-(OK1-A)") (class "Default")
      (node (ref "OK1") (pin "1") (pinfunction "A_1") (pintype "passive"))
      (node (ref "R25") (pin "2") (pinfunction "2_2") (pintype "passive"))
    )
    (net (code "68") (name "Net-(OK2-A)") (class "Default")
      (node (ref "OK2") (pin "1") (pinfunction "A_1") (pintype "passive"))
      (node (ref "R26") (pin "2") (pinfunction "2_2") (pintype "passive"))
    )
    (net (code "69") (name "Net-(OK3-A)") (class "Default")
      (node (ref "OK3") (pin "1") (pinfunction "A_1") (pintype "passive"))
      (node (ref "R27") (pin "2") (pinfunction "2_2") (pintype "passive"))
    )
    (net (code "70") (name "Net-(OK4-A)") (class "Default")
      (node (ref "OK4") (pin "1") (pinfunction "A_1") (pintype "passive"))
      (node (ref "R28") (pin "2") (pinfunction "2_2") (pintype "passive"))
    )
    (net (code "71") (name "Net-(OK5-A)") (class "Default")
      (node (ref "OK5") (pin "1") (pinfunction "A_1") (pintype "passive"))
      (node (ref "R29") (pin "2") (pinfunction "2_2") (pintype "passive"))
    )
    (net (code "72") (name "Net-(OK6-A)") (class "Default")
      (node (ref "OK6") (pin "1") (pinfunction "A_1") (pintype "passive"))
      (node (ref "R30") (pin "2") (pinfunction "2_2") (pintype "passive"))
    )
    (net (code "73") (name "Net-(OK7-A)") (class "Default")
      (node (ref "OK7") (pin "1") (pinfunction "A_1") (pintype "passive"))
      (node (ref "R31") (pin "2") (pinfunction "2_2") (pintype "passive"))
    )
    (net (code "74") (name "Net-(OK9-A)") (class "Default")
      (node (ref "C7") (pin "1") (pinfunction "1_1") (pintype "passive"))
      (node (ref "OK9") (pin "1") (pinfunction "A_1") (pintype "passive"))
      (node (ref "R1") (pin "2") (pinfunction "2_2") (pintype "passive"))
    )
    (net (code "75") (name "Net-(OK10-A)") (class "Default")
      (node (ref "C2") (pin "1") (pinfunction "1_1") (pintype "passive"))
      (node (ref "OK10") (pin "1") (pinfunction "A_1") (pintype "passive"))
      (node (ref "R3") (pin "2") (pinfunction "2_2") (pintype "passive"))
    )
    (net (code "76") (name "Net-(OK11-A)") (class "Default")
      (node (ref "C5") (pin "1") (pinfunction "1_1") (pintype "passive"))
      (node (ref "OK11") (pin "1") (pinfunction "A_1") (pintype "passive"))
      (node (ref "R5") (pin "2") (pinfunction "2_2") (pintype "passive"))
    )
    (net (code "77") (name "Net-(OK12-A)") (class "Default")
      (node (ref "C6") (pin "1") (pinfunction "1_1") (pintype "passive"))
      (node (ref "OK12") (pin "1") (pinfunction "A_1") (pintype "passive"))
      (node (ref "R7") (pin "2") (pinfunction "2_2") (pintype "passive"))
    )
    (net (code "78") (name "Net-(OK13-A)") (class "Default")
      (node (ref "C10") (pin "1") (pinfunction "1_1") (pintype "passive"))
      (node (ref "OK13") (pin "1") (pinfunction "A_1") (pintype "passive"))
      (node (ref "R9") (pin "2") (pinfunction "2_2") (pintype "passive"))
    )
    (net (code "79") (name "Net-(OK14-A)") (class "Default")
      (node (ref "C9") (pin "1") (pinfunction "1_1") (pintype "passive"))
      (node (ref "OK14") (pin "1") (pinfunction "A_1") (pintype "passive"))
      (node (ref "R11") (pin "2") (pinfunction "2_2") (pintype "passive"))
    )
    (net (code "80") (name "Net-(OK15-A)") (class "Default")
      (node (ref "C8") (pin "1") (pinfunction "1_1") (pintype "passive"))
      (node (ref "OK15") (pin "1") (pinfunction "A_1") (pintype "passive"))
      (node (ref "R13") (pin "2") (pinfunction "2_2") (pintype "passive"))
    )
    (net (code "81") (name "OK") (class "Default")
      (node (ref "IC1") (pin "16") (pinfunction "RC1/T1OSI/ICCP2/~{UOE}_16") (pintype "bidirectional"))
      (node (ref "R39") (pin "1") (pinfunction "1_1") (pintype "passive"))
    )
    (net (code "82") (name "OP0") (class "Default")
      (node (ref "IC1") (pin "19") (pinfunction "RD0/SPP0_19") (pintype "bidirectional"))
      (node (ref "R22") (pin "1") (pinfunction "1_1") (pintype "passive"))
      (node (ref "R28") (pin "1") (pinfunction "1_1") (pintype "passive"))
    )
    (net (code "83") (name "OP1") (class "Default")
      (node (ref "IC1") (pin "20") (pinfunction "RD1/SPP1_20") (pintype "bidirectional"))
      (node (ref "R23") (pin "1") (pinfunction "1_1") (pintype "passive"))
      (node (ref "R27") (pin "1") (pinfunction "1_1") (pintype "passive"))
    )
    (net (code "84") (name "OP2") (class "Default")
      (node (ref "IC1") (pin "21") (pinfunction "RD2/SPP2_21") (pintype "bidirectional"))
      (node (ref "R24") (pin "1") (pinfunction "1_1") (pintype "passive"))
      (node (ref "R25") (pin "1") (pinfunction "1_1") (pintype "passive"))
    )
    (net (code "85") (name "OP3") (class "Default")
      (node (ref "IC1") (pin "22") (pinfunction "RD3/SPP3_22") (pintype "bidirectional"))
      (node (ref "R26") (pin "1") (pinfunction "1_1") (pintype "passive"))
      (node (ref "R32") (pin "1") (pinfunction "1_1") (pintype "passive"))
    )
    (net (code "86") (name "OP4") (class "Default")
      (node (ref "IC1") (pin "27") (pinfunction "RD4/SPP4_27") (pintype "bidirectional"))
      (node (ref "R29") (pin "1") (pinfunction "1_1") (pintype "passive"))
      (node (ref "R34") (pin "1") (pinfunction "1_1") (pintype "passive"))
    )
    (net (code "87") (name "OP5") (class "Default")
      (node (ref "IC1") (pin "28") (pinfunction "RD5/SPP5/P1B_28") (pintype "bidirectional"))
      (node (ref "R30") (pin "1") (pinfunction "1_1") (pintype "passive"))
      (node (ref "R35") (pin "1") (pinfunction "1_1") (pintype "passive"))
    )
    (net (code "88") (name "OP6") (class "Default")
      (node (ref "IC1") (pin "29") (pinfunction "RD6/SPP6/P1C_29") (pintype "bidirectional"))
      (node (ref "R31") (pin "1") (pinfunction "1_1") (pintype "passive"))
      (node (ref "R36") (pin "1") (pinfunction "1_1") (pintype "passive"))
    )
    (net (code "89") (name "OSC1") (class "Default")
      (node (ref "20M") (pin "2") (pinfunction "2_2") (pintype "passive"))
      (node (ref "C3") (pin "2") (pinfunction "2_2") (pintype "passive"))
      (node (ref "IC1") (pin "14") (pinfunction "RA6/OSC2/CLKO_14") (pintype "output"))
    )
    (net (code "90") (name "OSC2") (class "Default")
      (node (ref "20M") (pin "1") (pinfunction "1_1") (pintype "passive"))
      (node (ref "C4") (pin "2") (pinfunction "2_2") (pintype "passive"))
      (node (ref "IC1") (pin "13") (pinfunction "OSC1/CLKI_13") (pintype "input"))
    )
    (net (code "91") (name "PGD") (class "Default")
      (node (ref "IC1") (pin "40") (pinfunction "RB7/BKI3/PGD_40") (pintype "bidirectional"))
      (node (ref "J2") (pin "4") (pinfunction "4_4") (pintype "passive"))
    )
    (net (code "92") (name "POW") (class "Default")
      (node (ref "IC1") (pin "15") (pinfunction "RC0/TIOSO/T13CKI_15") (pintype "bidirectional"))
      (node (ref "R38") (pin "1") (pinfunction "1_1") (pintype "passive"))
    )
    (net (code "93") (name "REST") (class "Default")
      (node (ref "IC1") (pin "1") (pinfunction "~{MCLR}/VPP/RE3_1") (pintype "input"))
      (node (ref "J2") (pin "1") (pinfunction "1_1") (pintype "passive"))
      (node (ref "PAD1") (pin "P$1") (pinfunction "P_P$1") (pintype "passive"))
      (node (ref "R33") (pin "1") (pinfunction "1_1") (pintype "passive"))
    )
    (net (code "94") (name "VUSB") (class "Default")
      (node (ref "C1") (pin "+") (pinfunction "+_+") (pintype "passive"))
      (node (ref "IC1") (pin "18") (pinfunction "VUSB_18") (pintype "bidirectional"))
    )
    (net (code "95") (name "unconnected-(IC1-RA4{slash}T0CKI{slash}CIOUT{slash}RCV-Pad6)") (class "Default")
      (node (ref "IC1") (pin "6") (pinfunction "RA4/T0CKI/CIOUT/RCV_6") (pintype "bidirectional"))
    )
    (net (code "96") (name "unconnected-(IC1-RC2{slash}CCP1{slash}P1A-Pad17)") (class "Default")
      (node (ref "IC1") (pin "17") (pinfunction "RC2/CCP1/P1A_17") (pintype "bidirectional"))
    )
    (net (code "97") (name "unconnected-(IC1-RC6{slash}TX{slash}CK-Pad25)") (class "Default")
      (node (ref "IC1") (pin "25") (pinfunction "RC6/TX/CK_25") (pintype "bidirectional"))
    )
    (net (code "98") (name "unconnected-(IC1-RC7{slash}RX{slash}DT{slash}SDO-Pad26)") (class "Default")
      (node (ref "IC1") (pin "26") (pinfunction "RC7/RX/DT/SDO_26") (pintype "bidirectional"))
    )
    (net (code "99") (name "unconnected-(IC1-RD7{slash}SPP7{slash}P1D-Pad30)") (class "Default")
      (node (ref "IC1") (pin "30") (pinfunction "RD7/SPP7/P1D_30") (pintype "bidirectional"))
    )
    (net (code "100") (name "unconnected-(IC1-RE2{slash}AN7{slash}OESPP-Pad10)") (class "Default")
      (node (ref "IC1") (pin "10") (pinfunction "RE2/AN7/OESPP_10") (pintype "bidirectional"))
    )
  )
)
